# microcontroller.net
KiCad netlist of a schematic drawn in Altium Designer
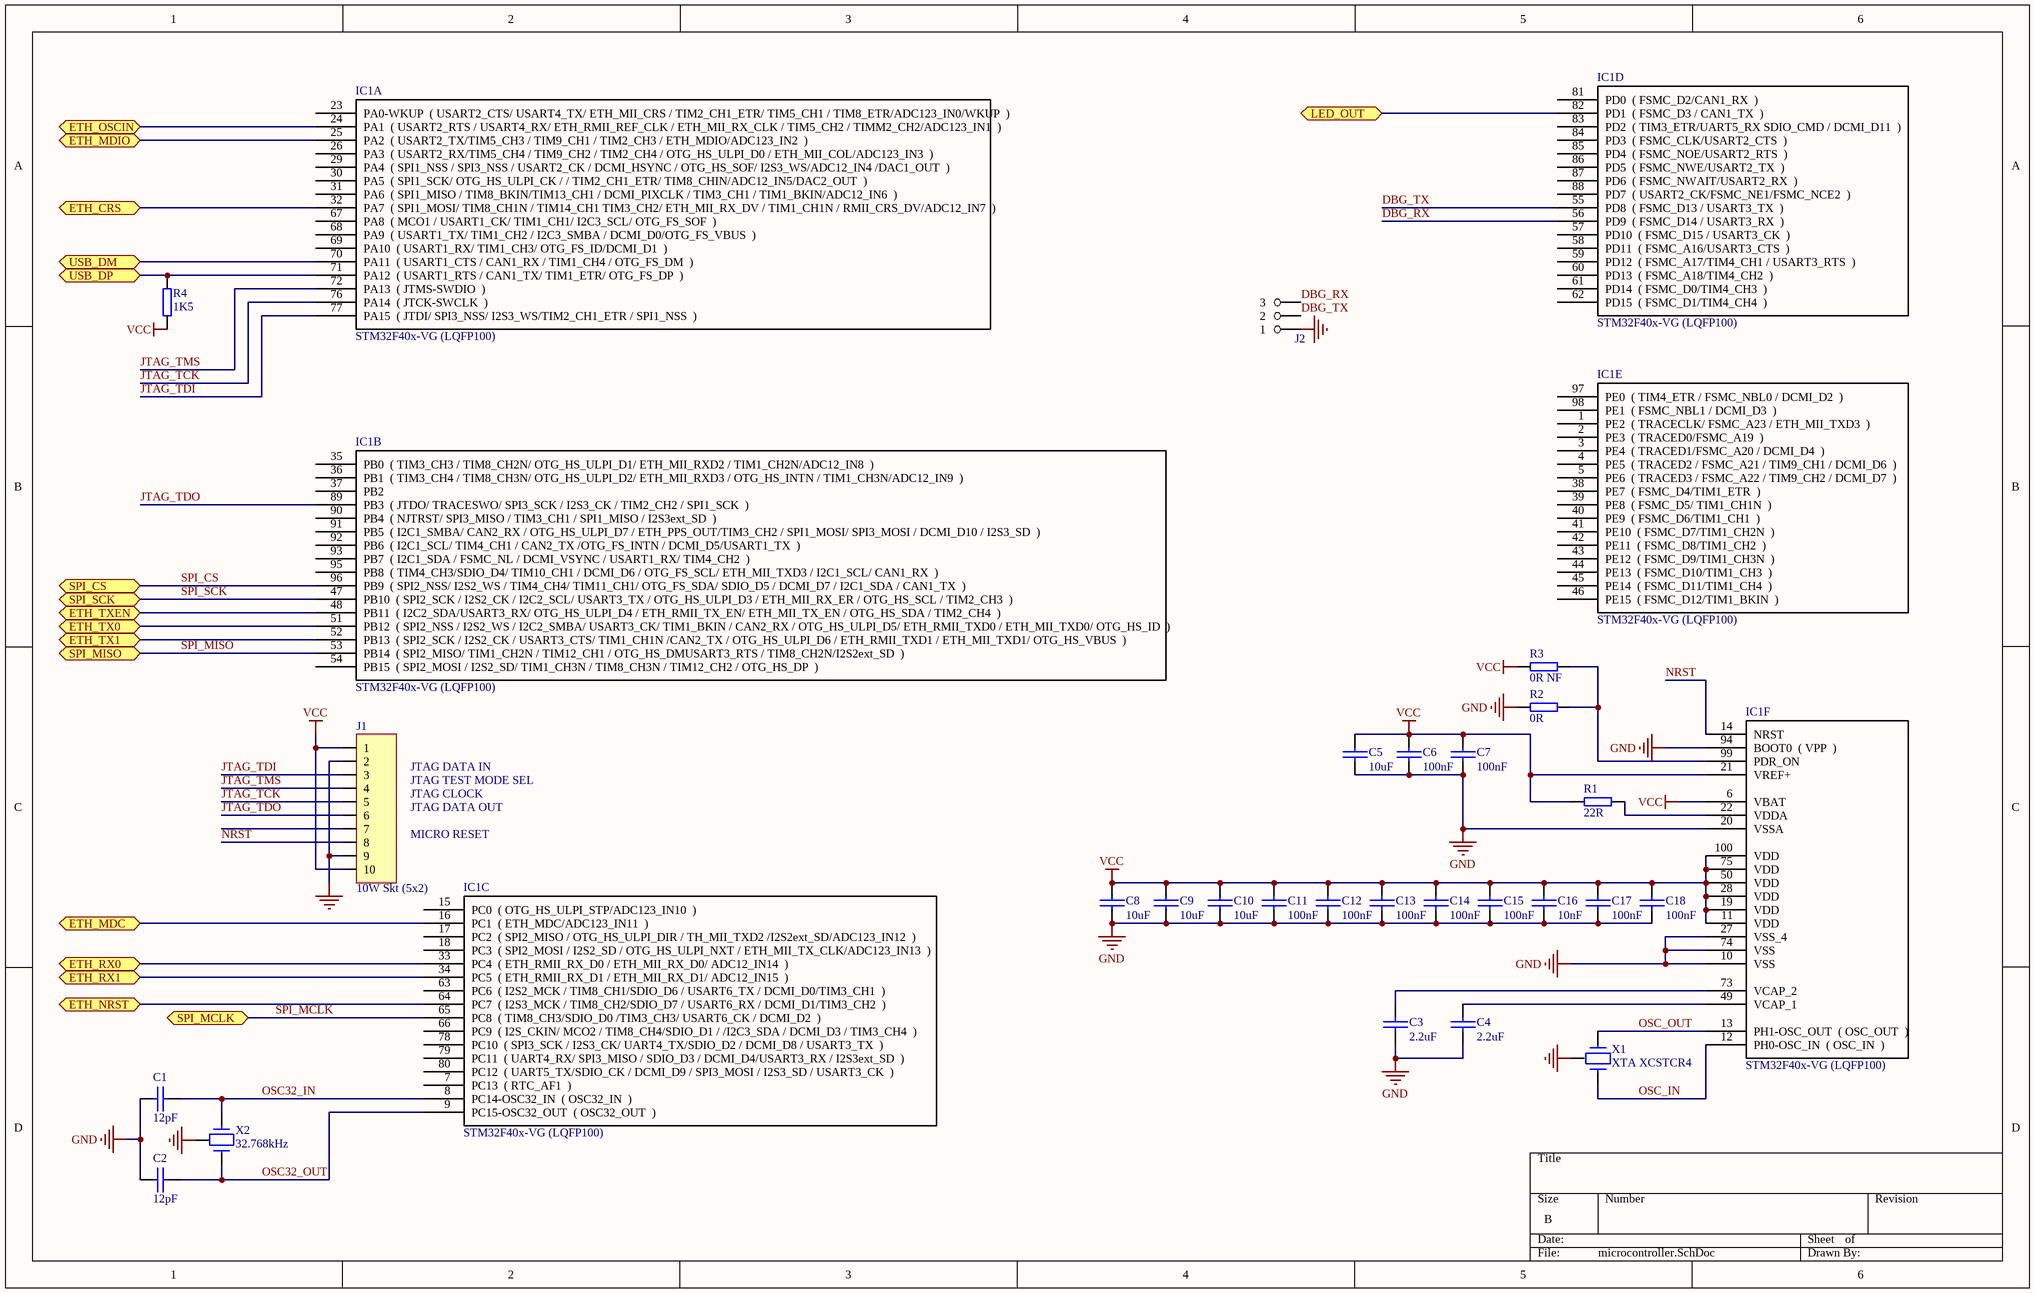
[diagram p0: microcontroller.SchDoc]

(export (version "E")
  (design (tool "Eeschema 10.0.6"))
  (components
    (comp (ref "C1")
      (value "12pF")
      (footprint "0603-IPC")
      (description "0.01uF 50V")
      (libsource (lib "NAUTECH SCHEMATIC") (part "CAP 0603 XXX"))
    )
    (comp (ref "C2")
      (value "12pF")
      (footprint "0603-IPC")
      (description "0.01uF 50V")
      (libsource (lib "NAUTECH SCHEMATIC") (part "CAP 0603 XXX"))
    )
    (comp (ref "C3")
      (value "2.2uF")
      (footprint "0603-IPC")
      (description "0.01uF 50V")
      (libsource (lib "NAUTECH SCHEMATIC") (part "CAP 0603 XXX"))
    )
    (comp (ref "C4")
      (value "2.2uF")
      (footprint "0603-IPC")
      (description "0.01uF 50V")
      (libsource (lib "NAUTECH SCHEMATIC") (part "CAP 0603 XXX"))
    )
    (comp (ref "C5")
      (value "10uF")
      (footprint "0603-IPC")
      (description "0.01uF 50V")
      (libsource (lib "NAUTECH SCHEMATIC") (part "CAP 0603 XXX"))
    )
    (comp (ref "C6")
      (value "100nF")
      (footprint "0603-IPC")
      (description "0.01uF 50V")
      (libsource (lib "NAUTECH SCHEMATIC") (part "CAP 0603 XXX"))
    )
    (comp (ref "C7")
      (value "100nF")
      (footprint "0603-IPC")
      (description "0.01uF 50V")
      (libsource (lib "NAUTECH SCHEMATIC") (part "CAP 0603 XXX"))
    )
    (comp (ref "C8")
      (value "10uF")
      (footprint "0603-IPC")
      (description "0.01uF 50V")
      (libsource (lib "NAUTECH SCHEMATIC") (part "CAP 0603 XXX"))
    )
    (comp (ref "C9")
      (value "10uF")
      (footprint "0603-IPC")
      (description "0.01uF 50V")
      (libsource (lib "NAUTECH SCHEMATIC") (part "CAP 0603 XXX"))
    )
    (comp (ref "C10")
      (value "10uF")
      (footprint "0603-IPC")
      (description "0.01uF 50V")
      (libsource (lib "NAUTECH SCHEMATIC") (part "CAP 0603 XXX"))
    )
    (comp (ref "C11")
      (value "100nF")
      (footprint "0603-IPC")
      (description "0.01uF 50V")
      (libsource (lib "NAUTECH SCHEMATIC") (part "CAP 0603 XXX"))
    )
    (comp (ref "C12")
      (value "100nF")
      (footprint "0603-IPC")
      (description "0.01uF 50V")
      (libsource (lib "NAUTECH SCHEMATIC") (part "CAP 0603 XXX"))
    )
    (comp (ref "C13")
      (value "100nF")
      (footprint "0603-IPC")
      (description "0.01uF 50V")
      (libsource (lib "NAUTECH SCHEMATIC") (part "CAP 0603 XXX"))
    )
    (comp (ref "C14")
      (value "100nF")
      (footprint "0603-IPC")
      (description "0.01uF 50V")
      (libsource (lib "NAUTECH SCHEMATIC") (part "CAP 0603 XXX"))
    )
    (comp (ref "C15")
      (value "100nF")
      (footprint "0603-IPC")
      (description "0.01uF 50V")
      (libsource (lib "NAUTECH SCHEMATIC") (part "CAP 0603 XXX"))
    )
    (comp (ref "C16")
      (value "10nF")
      (footprint "0603-IPC")
      (description "0.01uF 50V")
      (libsource (lib "NAUTECH SCHEMATIC") (part "CAP 0603 XXX"))
    )
    (comp (ref "C17")
      (value "100nF")
      (footprint "0603-IPC")
      (description "0.01uF 50V")
      (libsource (lib "NAUTECH SCHEMATIC") (part "CAP 0603 XXX"))
    )
    (comp (ref "C18")
      (value "100nF")
      (footprint "0603-IPC")
      (description "0.01uF 50V")
      (libsource (lib "NAUTECH SCHEMATIC") (part "CAP 0603 XXX"))
    )
    (comp (ref "IC1")
      (value "STM32F40x-VG (LQFP100)")
      (footprint "TQFP100_N")
      (libsource (lib "corporatecam") (part "STM32F40x-VG"))
    )
    (comp (ref "J1")
      (value "10W Skt (5x2)")
      (footprint "CON 10W 2mm IDC SKT")
      (description "CON 10W(2x5) SKT 2mm Vert H4.5mm")
      (fields (field (name "MANUFACTURER") "Harwin"))
      (libsource (lib "corporatecam") (part "CON 10W RECEPT 2mm"))
    )
    (comp (ref "J2")
      (value "Jumper 3W")
      (footprint "Jumper 2.54mm Pitch 3W")
      (description "3W Jumper Pitch 2.54mm")
      (libsource (lib "corporatecam") (part "Jumper 3W"))
    )
    (comp (ref "R1")
      (value "22R")
      (footprint "0603-IPC")
      (description "RES0603")
      (libsource (lib "NAUTECH SCHEMATIC") (part "RES 0603 XXX"))
    )
    (comp (ref "R2")
      (value "0R")
      (footprint "0603-IPC")
      (description "RES0603")
      (libsource (lib "NAUTECH SCHEMATIC") (part "RES 0603 XXX"))
    )
    (comp (ref "R3")
      (value "0R NF")
      (footprint "0603-IPC")
      (description "RES0603")
      (libsource (lib "NAUTECH SCHEMATIC") (part "RES 0603 XXX"))
    )
    (comp (ref "R4")
      (value "1K5")
      (footprint "0603-IPC")
      (description "RES0603")
      (libsource (lib "NAUTECH SCHEMATIC") (part "RES 0603 XXX"))
    )
    (comp (ref "X1")
      (value "XTA XCSTCR4")
      (footprint "XTA CSTCEXXX")
      (description "Murata Crystal Resonator 3.2mm x 1.3mm")
      (libsource (lib "corporatecam") (part "XTA CSTCEXXX"))
    )
    (comp (ref "X2")
      (value "32.768kHz")
      (footprint "X3-308")
      (description "32.768kHz Crystal 6.2 x 02.1MM CYLINDER")
      (libsource (lib "HVAC") (part "XTA 32.768kHz 6.2 x 02.1MM CYLINDER"))
    )
  )
  (nets
    (net (code "1") (name "/DBG_RX") (class "Default")
      (node (ref "IC1") (pin "56") (pinfunction "PD9__(_FSMC_D14_/_USART3_RX__)_56") (pintype "passive"))
      (node (ref "J2") (pin "3") (pinfunction "3_3") (pintype "passive"))
    )
    (net (code "2") (name "/DBG_TX") (class "Default")
      (node (ref "IC1") (pin "55") (pinfunction "PD8__(_FSMC_D13_/_USART3_TX__)_55") (pintype "passive"))
      (node (ref "J2") (pin "2") (pinfunction "2_2") (pintype "passive"))
    )
    (net (code "3") (name "/ETH_CRS") (class "Default")
      (node (ref "IC1") (pin "32") (pinfunction "PA7__(_SPI1_MOSI/_TIM8_CH1N_/_TIM14_CH1_TIM3_CH2/_ETH_MII_RX_DV_/_TIM1_CH1N_/_RMII_CRS_DV/ADC12_IN7__)_32") (pintype "passive"))
    )
    (net (code "4") (name "/ETH_MDC") (class "Default")
      (node (ref "IC1") (pin "16") (pinfunction "PC1__(_ETH_MDC/ADC123_IN11__)_16") (pintype "passive"))
    )
    (net (code "5") (name "/ETH_MDIO") (class "Default")
      (node (ref "IC1") (pin "25") (pinfunction "PA2__(_USART2_TX/TIM5_CH3_/_TIM9_CH1_/_TIM2_CH3_/_ETH_MDIO/ADC123_IN2__)_25") (pintype "passive"))
    )
    (net (code "6") (name "/ETH_NRST") (class "Default")
      (node (ref "IC1") (pin "64") (pinfunction "PC7__(_I2S3_MCK_/_TIM8_CH2/SDIO_D7_/_USART6_RX_/_DCMI_D1/TIM3_CH2__)_64") (pintype "passive"))
    )
    (net (code "7") (name "/ETH_OSCIN") (class "Default")
      (node (ref "IC1") (pin "24") (pinfunction "PA1__(_USART2_RTS_/_USART4_RX/_ETH_RMII_REF_CLK_/_ETH_MII_RX_CLK_/_TIM5_CH2_/_TIMM2_CH2/ADC123_IN1__)_24") (pintype "passive"))
    )
    (net (code "8") (name "/ETH_RX0") (class "Default")
      (node (ref "IC1") (pin "33") (pinfunction "PC4__(_ETH_RMII_RX_D0_/_ETH_MII_RX_D0/_ADC12_IN14__)_33") (pintype "passive"))
    )
    (net (code "9") (name "/ETH_RX1") (class "Default")
      (node (ref "IC1") (pin "34") (pinfunction "PC5__(_ETH_RMII_RX_D1_/_ETH_MII_RX_D1/_ADC12_IN15__)_34") (pintype "passive"))
    )
    (net (code "10") (name "/ETH_TX0") (class "Default")
      (node (ref "IC1") (pin "51") (pinfunction "PB12__(_SPI2_NSS_/_I2S2_WS_/_I2C2_SMBA/_USART3_CK/_TIM1_BKIN_/_CAN2_RX_/_OTG_HS_ULPI_D5/_ETH_RMII_TXD0_/_ETH_MII_TXD0/_OTG_HS_ID__)_51") (pintype "passive"))
    )
    (net (code "11") (name "/ETH_TX1") (class "Default")
      (node (ref "IC1") (pin "52") (pinfunction "PB13__(_SPI2_SCK_/_I2S2_CK_/_USART3_CTS/_TIM1_CH1N_/CAN2_TX_/_OTG_HS_ULPI_D6_/_ETH_RMII_TXD1_/_ETH_MII_TXD1/_OTG_HS_VBUS__)_52") (pintype "passive"))
    )
    (net (code "12") (name "/ETH_TXEN") (class "Default")
      (node (ref "IC1") (pin "48") (pinfunction "PB11__(_I2C2_SDA/USART3_RX/_OTG_HS_ULPI_D4_/_ETH_RMII_TX_EN/_ETH_MII_TX_EN_/_OTG_HS_SDA_/_TIM2_CH4__)_48") (pintype "passive"))
    )
    (net (code "13") (name "/JTAG_TCK") (class "Default")
      (node (ref "IC1") (pin "76") (pinfunction "PA14__(_JTCK-SWCLK__)_76") (pintype "passive"))
      (node (ref "J1") (pin "5") (pinfunction "5_5") (pintype "passive"))
    )
    (net (code "14") (name "/JTAG_TDI") (class "Default")
      (node (ref "IC1") (pin "77") (pinfunction "PA15__(_JTDI/_SPI3_NSS/_I2S3_WS/TIM2_CH1_ETR_/_SPI1_NSS__)_77") (pintype "passive"))
      (node (ref "J1") (pin "3") (pinfunction "3_3") (pintype "passive"))
    )
    (net (code "15") (name "/JTAG_TDO") (class "Default")
      (node (ref "IC1") (pin "89") (pinfunction "PB3__(_JTDO/_TRACESWO/_SPI3_SCK_/_I2S3_CK_/_TIM2_CH2_/_SPI1_SCK__)_89") (pintype "passive"))
      (node (ref "J1") (pin "6") (pinfunction "6_6") (pintype "passive"))
    )
    (net (code "16") (name "/JTAG_TMS") (class "Default")
      (node (ref "IC1") (pin "72") (pinfunction "PA13__(_JTMS-SWDIO__)_72") (pintype "passive"))
      (node (ref "J1") (pin "4") (pinfunction "4_4") (pintype "passive"))
    )
    (net (code "17") (name "/LED_OUT") (class "Default")
      (node (ref "IC1") (pin "82") (pinfunction "PD1__(_FSMC_D3_/_CAN1_TX__)_82") (pintype "passive"))
    )
    (net (code "18") (name "/NRST") (class "Default")
      (node (ref "IC1") (pin "14") (pinfunction "NRST_14") (pintype "passive"))
      (node (ref "J1") (pin "8") (pinfunction "8_8") (pintype "passive"))
    )
    (net (code "19") (name "/OSC32_IN") (class "Default")
      (node (ref "C1") (pin "2") (pintype "passive"))
      (node (ref "IC1") (pin "8") (pinfunction "PC14-OSC32_IN__(_OSC32_IN__)_8") (pintype "passive"))
      (node (ref "X2") (pin "2") (pintype "passive"))
    )
    (net (code "20") (name "/OSC32_OUT") (class "Default")
      (node (ref "C2") (pin "2") (pintype "passive"))
      (node (ref "IC1") (pin "9") (pinfunction "PC15-OSC32_OUT__(_OSC32_OUT__)_9") (pintype "passive"))
      (node (ref "X2") (pin "1") (pintype "passive"))
    )
    (net (code "21") (name "/OSC_IN") (class "Default")
      (node (ref "IC1") (pin "12") (pinfunction "PH0-OSC_IN__(_OSC_IN__)_12") (pintype "passive"))
      (node (ref "X1") (pin "3") (pintype "passive"))
    )
    (net (code "22") (name "/OSC_OUT") (class "Default")
      (node (ref "IC1") (pin "13") (pinfunction "PH1-OSC_OUT__(_OSC_OUT__)_13") (pintype "passive"))
      (node (ref "X1") (pin "1") (pintype "passive"))
    )
    (net (code "23") (name "/SPI_CS") (class "Default")
      (node (ref "IC1") (pin "96") (pinfunction "PB9__(_SPI2_NSS/_I2S2_WS_/_TIM4_CH4/_TIM11_CH1/_OTG_FS_SDA/_SDIO_D5_/_DCMI_D7_/_I2C1_SDA_/_CAN1_TX__)_96") (pintype "passive"))
    )
    (net (code "24") (name "/SPI_MCLK") (class "Default")
      (node (ref "IC1") (pin "65") (pinfunction "PC8__(_TIM8_CH3/SDIO_D0_/TIM3_CH3/_USART6_CK_/_DCMI_D2__)_65") (pintype "passive"))
    )
    (net (code "25") (name "/SPI_MISO") (class "Default")
      (node (ref "IC1") (pin "53") (pinfunction "PB14__(_SPI2_MISO/_TIM1_CH2N_/_TIM12_CH1_/_OTG_HS_DMUSART3_RTS_/_TIM8_CH2N/I2S2ext_SD__)_53") (pintype "passive"))
    )
    (net (code "26") (name "/SPI_SCK") (class "Default")
      (node (ref "IC1") (pin "47") (pinfunction "PB10__(_SPI2_SCK_/_I2S2_CK_/_I2C2_SCL/_USART3_TX_/_OTG_HS_ULPI_D3_/_ETH_MII_RX_ER_/_OTG_HS_SCL_/_TIM2_CH3__)_47") (pintype "passive"))
    )
    (net (code "27") (name "/USB_DM") (class "Default")
      (node (ref "IC1") (pin "70") (pinfunction "PA11__(_USART1_CTS_/_CAN1_RX_/_TIM1_CH4_/_OTG_FS_DM__)_70") (pintype "passive"))
    )
    (net (code "28") (name "/USB_DP") (class "Default")
      (node (ref "IC1") (pin "71") (pinfunction "PA12__(_USART1_RTS_/_CAN1_TX/_TIM1_ETR/_OTG_FS_DP__)_71") (pintype "passive"))
      (node (ref "R4") (pin "1") (pinfunction "1_1") (pintype "passive"))
    )
    (net (code "29") (name "GND") (class "Default")
      (node (ref "C1") (pin "1") (pintype "passive"))
      (node (ref "C10") (pin "1") (pintype "passive"))
      (node (ref "C11") (pin "1") (pintype "passive"))
      (node (ref "C12") (pin "1") (pintype "passive"))
      (node (ref "C13") (pin "1") (pintype "passive"))
      (node (ref "C14") (pin "1") (pintype "passive"))
      (node (ref "C15") (pin "1") (pintype "passive"))
      (node (ref "C16") (pin "1") (pintype "passive"))
      (node (ref "C17") (pin "1") (pintype "passive"))
      (node (ref "C18") (pin "1") (pintype "passive"))
      (node (ref "C2") (pin "1") (pintype "passive"))
      (node (ref "C3") (pin "1") (pintype "passive"))
      (node (ref "C4") (pin "1") (pintype "passive"))
      (node (ref "C5") (pin "1") (pintype "passive"))
      (node (ref "C6") (pin "1") (pintype "passive"))
      (node (ref "C7") (pin "1") (pintype "passive"))
      (node (ref "C8") (pin "1") (pintype "passive"))
      (node (ref "C9") (pin "1") (pintype "passive"))
      (node (ref "IC1") (pin "10") (pinfunction "VSS_10") (pintype "passive"))
      (node (ref "IC1") (pin "20") (pinfunction "VSSA_20") (pintype "passive"))
      (node (ref "IC1") (pin "27") (pinfunction "VSS_4_27") (pintype "passive"))
      (node (ref "IC1") (pin "74") (pinfunction "VSS_74") (pintype "passive"))
      (node (ref "IC1") (pin "94") (pinfunction "BOOT0__(_VPP__)_94") (pintype "passive"))
      (node (ref "J1") (pin "2") (pinfunction "2_2") (pintype "passive"))
      (node (ref "J1") (pin "9") (pinfunction "9_9") (pintype "passive"))
      (node (ref "J2") (pin "1") (pinfunction "1_1") (pintype "passive"))
      (node (ref "R2") (pin "2") (pinfunction "2_2") (pintype "passive"))
      (node (ref "X1") (pin "2") (pintype "power_in"))
      (node (ref "X2") (pin "3") (pintype "passive"))
    )
    (net (code "30") (name "Net-(IC1F-PDR_ON)") (class "Default")
      (node (ref "IC1") (pin "99") (pinfunction "PDR_ON_99") (pintype "passive"))
      (node (ref "R2") (pin "1") (pinfunction "1_1") (pintype "passive"))
      (node (ref "R3") (pin "1") (pinfunction "1_1") (pintype "passive"))
    )
    (net (code "31") (name "Net-(IC1F-VCAP_1)") (class "Default")
      (node (ref "C4") (pin "2") (pintype "passive"))
      (node (ref "IC1") (pin "49") (pinfunction "VCAP_1_49") (pintype "passive"))
    )
    (net (code "32") (name "Net-(IC1F-VCAP_2)") (class "Default")
      (node (ref "C3") (pin "2") (pintype "passive"))
      (node (ref "IC1") (pin "73") (pinfunction "VCAP_2_73") (pintype "passive"))
    )
    (net (code "33") (name "Net-(IC1F-VDDA)") (class "Default")
      (node (ref "IC1") (pin "22") (pinfunction "VDDA_22") (pintype "passive"))
      (node (ref "R1") (pin "1") (pinfunction "1_1") (pintype "passive"))
    )
    (net (code "34") (name "VCC") (class "Default")
      (node (ref "C10") (pin "2") (pintype "passive"))
      (node (ref "C11") (pin "2") (pintype "passive"))
      (node (ref "C12") (pin "2") (pintype "passive"))
      (node (ref "C13") (pin "2") (pintype "passive"))
      (node (ref "C14") (pin "2") (pintype "passive"))
      (node (ref "C15") (pin "2") (pintype "passive"))
      (node (ref "C16") (pin "2") (pintype "passive"))
      (node (ref "C17") (pin "2") (pintype "passive"))
      (node (ref "C18") (pin "2") (pintype "passive"))
      (node (ref "C5") (pin "2") (pintype "passive"))
      (node (ref "C6") (pin "2") (pintype "passive"))
      (node (ref "C7") (pin "2") (pintype "passive"))
      (node (ref "C8") (pin "2") (pintype "passive"))
      (node (ref "C9") (pin "2") (pintype "passive"))
      (node (ref "IC1") (pin "100") (pinfunction "VDD_100") (pintype "passive"))
      (node (ref "IC1") (pin "11") (pinfunction "VDD_11") (pintype "passive"))
      (node (ref "IC1") (pin "19") (pinfunction "VDD_19") (pintype "passive"))
      (node (ref "IC1") (pin "21") (pinfunction "VREF+_21") (pintype "passive"))
      (node (ref "IC1") (pin "28") (pinfunction "VDD_28") (pintype "passive"))
      (node (ref "IC1") (pin "50") (pinfunction "VDD_50") (pintype "passive"))
      (node (ref "IC1") (pin "6") (pinfunction "VBAT_6") (pintype "passive"))
      (node (ref "IC1") (pin "75") (pinfunction "VDD_75") (pintype "passive"))
      (node (ref "J1") (pin "1") (pinfunction "1_1") (pintype "passive"))
      (node (ref "J1") (pin "10") (pinfunction "10_10") (pintype "passive"))
      (node (ref "R1") (pin "2") (pinfunction "2_2") (pintype "passive"))
      (node (ref "R3") (pin "2") (pinfunction "2_2") (pintype "passive"))
      (node (ref "R4") (pin "2") (pinfunction "2_2") (pintype "passive"))
    )
    (net (code "35") (name "unconnected-(IC1A-PA0-WKUP__(_USART2_CTS{slash}_USART4_TX{slash}_ETH_MII_CRS_{slash}_TIM2_CH1_ETR{slash}_TIM5_CH1_{slash}_TIM8_ETR{slash}ADC123_IN0{slash}WKUP__)-Pad23)") (class "Default")
      (node (ref "IC1") (pin "23") (pinfunction "PA0-WKUP__(_USART2_CTS/_USART4_TX/_ETH_MII_CRS_/_TIM2_CH1_ETR/_TIM5_CH1_/_TIM8_ETR/ADC123_IN0/WKUP__)_23") (pintype "passive"))
    )
    (net (code "36") (name "unconnected-(IC1A-PA3__(_USART2_RX{slash}TIM5_CH4_{slash}_TIM9_CH2_{slash}_TIM2_CH4_{slash}_OTG_HS_ULPI_D0_{slash}_ETH_MII_COL{slash}ADC123_IN3__)-Pad26)") (class "Default")
      (node (ref "IC1") (pin "26") (pinfunction "PA3__(_USART2_RX/TIM5_CH4_/_TIM9_CH2_/_TIM2_CH4_/_OTG_HS_ULPI_D0_/_ETH_MII_COL/ADC123_IN3__)_26") (pintype "passive"))
    )
    (net (code "37") (name "unconnected-(IC1A-PA4__(_SPI1_NSS_{slash}_SPI3_NSS_{slash}_USART2_CK_{slash}_DCMI_HSYNC_{slash}_OTG_HS_SOF{slash}_I2S3_WS{slash}ADC12_IN4_{slash}DAC1_OUT__)-Pad29)") (class "Default")
      (node (ref "IC1") (pin "29") (pinfunction "PA4__(_SPI1_NSS_/_SPI3_NSS_/_USART2_CK_/_DCMI_HSYNC_/_OTG_HS_SOF/_I2S3_WS/ADC12_IN4_/DAC1_OUT__)_29") (pintype "passive"))
    )
    (net (code "38") (name "unconnected-(IC1A-PA5__(_SPI1_SCK{slash}_OTG_HS_ULPI_CK_{slash}_{slash}_TIM2_CH1_ETR{slash}_TIM8_CHIN{slash}ADC12_IN5{slash}DAC2_OUT__)-Pad30)") (class "Default")
      (node (ref "IC1") (pin "30") (pinfunction "PA5__(_SPI1_SCK/_OTG_HS_ULPI_CK_/_/_TIM2_CH1_ETR/_TIM8_CHIN/ADC12_IN5/DAC2_OUT__)_30") (pintype "passive"))
    )
    (net (code "39") (name "unconnected-(IC1A-PA6__(_SPI1_MISO_{slash}_TIM8_BKIN{slash}TIM13_CH1_{slash}_DCMI_PIXCLK_{slash}_TIM3_CH1_{slash}_TIM1_BKIN{slash}ADC12_IN6__)-Pad31)") (class "Default")
      (node (ref "IC1") (pin "31") (pinfunction "PA6__(_SPI1_MISO_/_TIM8_BKIN/TIM13_CH1_/_DCMI_PIXCLK_/_TIM3_CH1_/_TIM1_BKIN/ADC12_IN6__)_31") (pintype "passive"))
    )
    (net (code "40") (name "unconnected-(IC1A-PA8__(_MCO1_{slash}_USART1_CK{slash}_TIM1_CH1{slash}_I2C3_SCL{slash}_OTG_FS_SOF__)-Pad67)") (class "Default")
      (node (ref "IC1") (pin "67") (pinfunction "PA8__(_MCO1_/_USART1_CK/_TIM1_CH1/_I2C3_SCL/_OTG_FS_SOF__)_67") (pintype "passive"))
    )
    (net (code "41") (name "unconnected-(IC1A-PA9__(_USART1_TX{slash}_TIM1_CH2_{slash}_I2C3_SMBA_{slash}_DCMI_D0{slash}OTG_FS_VBUS__)-Pad68)") (class "Default")
      (node (ref "IC1") (pin "68") (pinfunction "PA9__(_USART1_TX/_TIM1_CH2_/_I2C3_SMBA_/_DCMI_D0/OTG_FS_VBUS__)_68") (pintype "passive"))
    )
    (net (code "42") (name "unconnected-(IC1A-PA10__(_USART1_RX{slash}_TIM1_CH3{slash}_OTG_FS_ID{slash}DCMI_D1__)-Pad69)") (class "Default")
      (node (ref "IC1") (pin "69") (pinfunction "PA10__(_USART1_RX/_TIM1_CH3/_OTG_FS_ID/DCMI_D1__)_69") (pintype "passive"))
    )
    (net (code "43") (name "unconnected-(IC1B-PB0__(_TIM3_CH3_{slash}_TIM8_CH2N{slash}_OTG_HS_ULPI_D1{slash}_ETH_MII_RXD2_{slash}_TIM1_CH2N{slash}ADC12_IN8__)-Pad35)") (class "Default")
      (node (ref "IC1") (pin "35") (pinfunction "PB0__(_TIM3_CH3_/_TIM8_CH2N/_OTG_HS_ULPI_D1/_ETH_MII_RXD2_/_TIM1_CH2N/ADC12_IN8__)_35") (pintype "passive"))
    )
    (net (code "44") (name "unconnected-(IC1B-PB1__(_TIM3_CH4_{slash}_TIM8_CH3N{slash}_OTG_HS_ULPI_D2{slash}_ETH_MII_RXD3_{slash}_OTG_HS_INTN_{slash}_TIM1_CH3N{slash}ADC12_IN9__)-Pad36)") (class "Default")
      (node (ref "IC1") (pin "36") (pinfunction "PB1__(_TIM3_CH4_/_TIM8_CH3N/_OTG_HS_ULPI_D2/_ETH_MII_RXD3_/_OTG_HS_INTN_/_TIM1_CH3N/ADC12_IN9__)_36") (pintype "passive"))
    )
    (net (code "45") (name "unconnected-(IC1B-PB2-Pad37)") (class "Default")
      (node (ref "IC1") (pin "37") (pinfunction "PB2_37") (pintype "passive"))
    )
    (net (code "46") (name "unconnected-(IC1B-PB4__(_NJTRST{slash}_SPI3_MISO_{slash}_TIM3_CH1_{slash}_SPI1_MISO_{slash}_I2S3ext_SD__)-Pad90)") (class "Default")
      (node (ref "IC1") (pin "90") (pinfunction "PB4__(_NJTRST/_SPI3_MISO_/_TIM3_CH1_/_SPI1_MISO_/_I2S3ext_SD__)_90") (pintype "passive"))
    )
    (net (code "47") (name "unconnected-(IC1B-PB5__(_I2C1_SMBA{slash}_CAN2_RX_{slash}_OTG_HS_ULPI_D7_{slash}_ETH_PPS_OUT{slash}TIM3_CH2_{slash}_SPI1_MOSI{slash}_SPI3_MOSI_{slash}_DCMI_D10_{slash}_I2S3_SD__)-Pad91)") (class "Default")
      (node (ref "IC1") (pin "91") (pinfunction "PB5__(_I2C1_SMBA/_CAN2_RX_/_OTG_HS_ULPI_D7_/_ETH_PPS_OUT/TIM3_CH2_/_SPI1_MOSI/_SPI3_MOSI_/_DCMI_D10_/_I2S3_SD__)_91") (pintype "passive"))
    )
    (net (code "48") (name "unconnected-(IC1B-PB6__(_I2C1_SCL{slash}_TIM4_CH1_{slash}_CAN2_TX_{slash}OTG_FS_INTN_{slash}_DCMI_D5{slash}USART1_TX__)-Pad92)") (class "Default")
      (node (ref "IC1") (pin "92") (pinfunction "PB6__(_I2C1_SCL/_TIM4_CH1_/_CAN2_TX_/OTG_FS_INTN_/_DCMI_D5/USART1_TX__)_92") (pintype "passive"))
    )
    (net (code "49") (name "unconnected-(IC1B-PB7__(_I2C1_SDA_{slash}_FSMC_NL_{slash}_DCMI_VSYNC_{slash}_USART1_RX{slash}_TIM4_CH2__)-Pad93)") (class "Default")
      (node (ref "IC1") (pin "93") (pinfunction "PB7__(_I2C1_SDA_/_FSMC_NL_/_DCMI_VSYNC_/_USART1_RX/_TIM4_CH2__)_93") (pintype "passive"))
    )
    (net (code "50") (name "unconnected-(IC1B-PB8__(_TIM4_CH3{slash}SDIO_D4{slash}_TIM10_CH1_{slash}_DCMI_D6_{slash}_OTG_FS_SCL{slash}_ETH_MII_TXD3_{slash}_I2C1_SCL{slash}_CAN1_RX__)-Pad95)") (class "Default")
      (node (ref "IC1") (pin "95") (pinfunction "PB8__(_TIM4_CH3/SDIO_D4/_TIM10_CH1_/_DCMI_D6_/_OTG_FS_SCL/_ETH_MII_TXD3_/_I2C1_SCL/_CAN1_RX__)_95") (pintype "passive"))
    )
    (net (code "51") (name "unconnected-(IC1B-PB15__(_SPI2_MOSI_{slash}_I2S2_SD{slash}_TIM1_CH3N_{slash}_TIM8_CH3N_{slash}_TIM12_CH2_{slash}_OTG_HS_DP__)-Pad54)") (class "Default")
      (node (ref "IC1") (pin "54") (pinfunction "PB15__(_SPI2_MOSI_/_I2S2_SD/_TIM1_CH3N_/_TIM8_CH3N_/_TIM12_CH2_/_OTG_HS_DP__)_54") (pintype "passive"))
    )
    (net (code "52") (name "unconnected-(IC1C-PC0__(_OTG_HS_ULPI_STP{slash}ADC123_IN10__)-Pad15)") (class "Default")
      (node (ref "IC1") (pin "15") (pinfunction "PC0__(_OTG_HS_ULPI_STP/ADC123_IN10__)_15") (pintype "passive"))
    )
    (net (code "53") (name "unconnected-(IC1C-PC2__(_SPI2_MISO_{slash}_OTG_HS_ULPI_DIR_{slash}_TH_MII_TXD2_{slash}I2S2ext_SD{slash}ADC123_IN12__)-Pad17)") (class "Default")
      (node (ref "IC1") (pin "17") (pinfunction "PC2__(_SPI2_MISO_/_OTG_HS_ULPI_DIR_/_TH_MII_TXD2_/I2S2ext_SD/ADC123_IN12__)_17") (pintype "passive"))
    )
    (net (code "54") (name "unconnected-(IC1C-PC3__(_SPI2_MOSI_{slash}_I2S2_SD_{slash}_OTG_HS_ULPI_NXT_{slash}_ETH_MII_TX_CLK{slash}ADC123_IN13__)-Pad18)") (class "Default")
      (node (ref "IC1") (pin "18") (pinfunction "PC3__(_SPI2_MOSI_/_I2S2_SD_/_OTG_HS_ULPI_NXT_/_ETH_MII_TX_CLK/ADC123_IN13__)_18") (pintype "passive"))
    )
    (net (code "55") (name "unconnected-(IC1C-PC6__(_I2S2_MCK_{slash}_TIM8_CH1{slash}SDIO_D6_{slash}_USART6_TX_{slash}_DCMI_D0{slash}TIM3_CH1__)-Pad63)") (class "Default")
      (node (ref "IC1") (pin "63") (pinfunction "PC6__(_I2S2_MCK_/_TIM8_CH1/SDIO_D6_/_USART6_TX_/_DCMI_D0/TIM3_CH1__)_63") (pintype "passive"))
    )
    (net (code "56") (name "unconnected-(IC1C-PC9__(_I2S_CKIN{slash}_MCO2_{slash}_TIM8_CH4{slash}SDIO_D1_{slash}_{slash}I2C3_SDA_{slash}_DCMI_D3_{slash}_TIM3_CH4__)-Pad66)") (class "Default")
      (node (ref "IC1") (pin "66") (pinfunction "PC9__(_I2S_CKIN/_MCO2_/_TIM8_CH4/SDIO_D1_/_/I2C3_SDA_/_DCMI_D3_/_TIM3_CH4__)_66") (pintype "passive"))
    )
    (net (code "57") (name "unconnected-(IC1C-PC10__(_SPI3_SCK_{slash}_I2S3_CK{slash}_UART4_TX{slash}SDIO_D2_{slash}_DCMI_D8_{slash}_USART3_TX__)-Pad78)") (class "Default")
      (node (ref "IC1") (pin "78") (pinfunction "PC10__(_SPI3_SCK_/_I2S3_CK/_UART4_TX/SDIO_D2_/_DCMI_D8_/_USART3_TX__)_78") (pintype "passive"))
    )
    (net (code "58") (name "unconnected-(IC1C-PC11__(_UART4_RX{slash}_SPI3_MISO_{slash}_SDIO_D3_{slash}_DCMI_D4{slash}USART3_RX_{slash}_I2S3ext_SD__)-Pad79)") (class "Default")
      (node (ref "IC1") (pin "79") (pinfunction "PC11__(_UART4_RX/_SPI3_MISO_/_SDIO_D3_/_DCMI_D4/USART3_RX_/_I2S3ext_SD__)_79") (pintype "passive"))
    )
    (net (code "59") (name "unconnected-(IC1C-PC12__(_UART5_TX{slash}SDIO_CK_{slash}_DCMI_D9_{slash}_SPI3_MOSI_{slash}_I2S3_SD_{slash}_USART3_CK__)-Pad80)") (class "Default")
      (node (ref "IC1") (pin "80") (pinfunction "PC12__(_UART5_TX/SDIO_CK_/_DCMI_D9_/_SPI3_MOSI_/_I2S3_SD_/_USART3_CK__)_80") (pintype "passive"))
    )
    (net (code "60") (name "unconnected-(IC1C-PC13__(_RTC_AF1__)-Pad7)") (class "Default")
      (node (ref "IC1") (pin "7") (pinfunction "PC13__(_RTC_AF1__)_7") (pintype "passive"))
    )
    (net (code "61") (name "unconnected-(IC1D-PD0__(_FSMC_D2{slash}CAN1_RX__)-Pad81)") (class "Default")
      (node (ref "IC1") (pin "81") (pinfunction "PD0__(_FSMC_D2/CAN1_RX__)_81") (pintype "passive"))
    )
    (net (code "62") (name "unconnected-(IC1D-PD2__(_TIM3_ETR{slash}UART5_RX_SDIO_CMD_{slash}_DCMI_D11__)-Pad83)") (class "Default")
      (node (ref "IC1") (pin "83") (pinfunction "PD2__(_TIM3_ETR/UART5_RX_SDIO_CMD_/_DCMI_D11__)_83") (pintype "passive"))
    )
    (net (code "63") (name "unconnected-(IC1D-PD3__(_FSMC_CLK{slash}USART2_CTS__)-Pad84)") (class "Default")
      (node (ref "IC1") (pin "84") (pinfunction "PD3__(_FSMC_CLK/USART2_CTS__)_84") (pintype "passive"))
    )
    (net (code "64") (name "unconnected-(IC1D-PD4__(_FSMC_NOE{slash}USART2_RTS__)-Pad85)") (class "Default")
      (node (ref "IC1") (pin "85") (pinfunction "PD4__(_FSMC_NOE/USART2_RTS__)_85") (pintype "passive"))
    )
    (net (code "65") (name "unconnected-(IC1D-PD5__(_FSMC_NWE{slash}USART2_TX__)-Pad86)") (class "Default")
      (node (ref "IC1") (pin "86") (pinfunction "PD5__(_FSMC_NWE/USART2_TX__)_86") (pintype "passive"))
    )
    (net (code "66") (name "unconnected-(IC1D-PD6__(_FSMC_NWAIT{slash}USART2_RX__)-Pad87)") (class "Default")
      (node (ref "IC1") (pin "87") (pinfunction "PD6__(_FSMC_NWAIT/USART2_RX__)_87") (pintype "passive"))
    )
    (net (code "67") (name "unconnected-(IC1D-PD7__(_USART2_CK{slash}FSMC_NE1{slash}FSMC_NCE2__)-Pad88)") (class "Default")
      (node (ref "IC1") (pin "88") (pinfunction "PD7__(_USART2_CK/FSMC_NE1/FSMC_NCE2__)_88") (pintype "passive"))
    )
    (net (code "68") (name "unconnected-(IC1D-PD10__(_FSMC_D15_{slash}_USART3_CK__)-Pad57)") (class "Default")
      (node (ref "IC1") (pin "57") (pinfunction "PD10__(_FSMC_D15_/_USART3_CK__)_57") (pintype "passive"))
    )
    (net (code "69") (name "unconnected-(IC1D-PD11__(_FSMC_A16{slash}USART3_CTS__)-Pad58)") (class "Default")
      (node (ref "IC1") (pin "58") (pinfunction "PD11__(_FSMC_A16/USART3_CTS__)_58") (pintype "passive"))
    )
    (net (code "70") (name "unconnected-(IC1D-PD12__(_FSMC_A17{slash}TIM4_CH1_{slash}_USART3_RTS__)-Pad59)") (class "Default")
      (node (ref "IC1") (pin "59") (pinfunction "PD12__(_FSMC_A17/TIM4_CH1_/_USART3_RTS__)_59") (pintype "passive"))
    )
    (net (code "71") (name "unconnected-(IC1D-PD13__(_FSMC_A18{slash}TIM4_CH2__)-Pad60)") (class "Default")
      (node (ref "IC1") (pin "60") (pinfunction "PD13__(_FSMC_A18/TIM4_CH2__)_60") (pintype "passive"))
    )
    (net (code "72") (name "unconnected-(IC1D-PD14__(_FSMC_D0{slash}TIM4_CH3__)-Pad61)") (class "Default")
      (node (ref "IC1") (pin "61") (pinfunction "PD14__(_FSMC_D0/TIM4_CH3__)_61") (pintype "passive"))
    )
    (net (code "73") (name "unconnected-(IC1D-PD15__(_FSMC_D1{slash}TIM4_CH4__)-Pad62)") (class "Default")
      (node (ref "IC1") (pin "62") (pinfunction "PD15__(_FSMC_D1/TIM4_CH4__)_62") (pintype "passive"))
    )
    (net (code "74") (name "unconnected-(IC1E-PE0__(_TIM4_ETR_{slash}_FSMC_NBL0_{slash}_DCMI_D2__)-Pad97)") (class "Default")
      (node (ref "IC1") (pin "97") (pinfunction "PE0__(_TIM4_ETR_/_FSMC_NBL0_/_DCMI_D2__)_97") (pintype "passive"))
    )
    (net (code "75") (name "unconnected-(IC1E-PE1__(_FSMC_NBL1_{slash}_DCMI_D3__)-Pad98)") (class "Default")
      (node (ref "IC1") (pin "98") (pinfunction "PE1__(_FSMC_NBL1_/_DCMI_D3__)_98") (pintype "passive"))
    )
    (net (code "76") (name "unconnected-(IC1E-PE2__(_TRACECLK{slash}_FSMC_A23_{slash}_ETH_MII_TXD3__)-Pad1)") (class "Default")
      (node (ref "IC1") (pin "1") (pinfunction "PE2__(_TRACECLK/_FSMC_A23_/_ETH_MII_TXD3__)_1") (pintype "passive"))
    )
    (net (code "77") (name "unconnected-(IC1E-PE3__(_TRACED0{slash}FSMC_A19__)-Pad2)") (class "Default")
      (node (ref "IC1") (pin "2") (pinfunction "PE3__(_TRACED0/FSMC_A19__)_2") (pintype "passive"))
    )
    (net (code "78") (name "unconnected-(IC1E-PE4__(_TRACED1{slash}FSMC_A20_{slash}_DCMI_D4__)-Pad3)") (class "Default")
      (node (ref "IC1") (pin "3") (pinfunction "PE4__(_TRACED1/FSMC_A20_/_DCMI_D4__)_3") (pintype "passive"))
    )
    (net (code "79") (name "unconnected-(IC1E-PE5__(_TRACED2_{slash}_FSMC_A21_{slash}_TIM9_CH1_{slash}_DCMI_D6__)-Pad4)") (class "Default")
      (node (ref "IC1") (pin "4") (pinfunction "PE5__(_TRACED2_/_FSMC_A21_/_TIM9_CH1_/_DCMI_D6__)_4") (pintype "passive"))
    )
    (net (code "80") (name "unconnected-(IC1E-PE6__(_TRACED3_{slash}_FSMC_A22_{slash}_TIM9_CH2_{slash}_DCMI_D7__)-Pad5)") (class "Default")
      (node (ref "IC1") (pin "5") (pinfunction "PE6__(_TRACED3_/_FSMC_A22_/_TIM9_CH2_/_DCMI_D7__)_5") (pintype "passive"))
    )
    (net (code "81") (name "unconnected-(IC1E-PE7__(_FSMC_D4{slash}TIM1_ETR__)-Pad38)") (class "Default")
      (node (ref "IC1") (pin "38") (pinfunction "PE7__(_FSMC_D4/TIM1_ETR__)_38") (pintype "passive"))
    )
    (net (code "82") (name "unconnected-(IC1E-PE8__(_FSMC_D5{slash}_TIM1_CH1N__)-Pad39)") (class "Default")
      (node (ref "IC1") (pin "39") (pinfunction "PE8__(_FSMC_D5/_TIM1_CH1N__)_39") (pintype "passive"))
    )
    (net (code "83") (name "unconnected-(IC1E-PE9__(_FSMC_D6{slash}TIM1_CH1__)-Pad40)") (class "Default")
      (node (ref "IC1") (pin "40") (pinfunction "PE9__(_FSMC_D6/TIM1_CH1__)_40") (pintype "passive"))
    )
    (net (code "84") (name "unconnected-(IC1E-PE10__(_FSMC_D7{slash}TIM1_CH2N__)-Pad41)") (class "Default")
      (node (ref "IC1") (pin "41") (pinfunction "PE10__(_FSMC_D7/TIM1_CH2N__)_41") (pintype "passive"))
    )
    (net (code "85") (name "unconnected-(IC1E-PE11__(_FSMC_D8{slash}TIM1_CH2__)-Pad42)") (class "Default")
      (node (ref "IC1") (pin "42") (pinfunction "PE11__(_FSMC_D8/TIM1_CH2__)_42") (pintype "passive"))
    )
    (net (code "86") (name "unconnected-(IC1E-PE12__(_FSMC_D9{slash}TIM1_CH3N__)-Pad43)") (class "Default")
      (node (ref "IC1") (pin "43") (pinfunction "PE12__(_FSMC_D9/TIM1_CH3N__)_43") (pintype "passive"))
    )
    (net (code "87") (name "unconnected-(IC1E-PE13__(_FSMC_D10{slash}TIM1_CH3__)-Pad44)") (class "Default")
      (node (ref "IC1") (pin "44") (pinfunction "PE13__(_FSMC_D10/TIM1_CH3__)_44") (pintype "passive"))
    )
    (net (code "88") (name "unconnected-(IC1E-PE14__(_FSMC_D11{slash}TIM1_CH4__)-Pad45)") (class "Default")
      (node (ref "IC1") (pin "45") (pinfunction "PE14__(_FSMC_D11/TIM1_CH4__)_45") (pintype "passive"))
    )
    (net (code "89") (name "unconnected-(IC1E-PE15__(_FSMC_D12{slash}TIM1_BKIN__)-Pad46)") (class "Default")
      (node (ref "IC1") (pin "46") (pinfunction "PE15__(_FSMC_D12/TIM1_BKIN__)_46") (pintype "passive"))
    )
    (net (code "90") (name "unconnected-(J1-Pad7)") (class "Default")
      (node (ref "J1") (pin "7") (pinfunction "7_7") (pintype "passive"))
    )
  )
)
